# Signal.net
KiCad netlist of a schematic drawn in Altium Designer
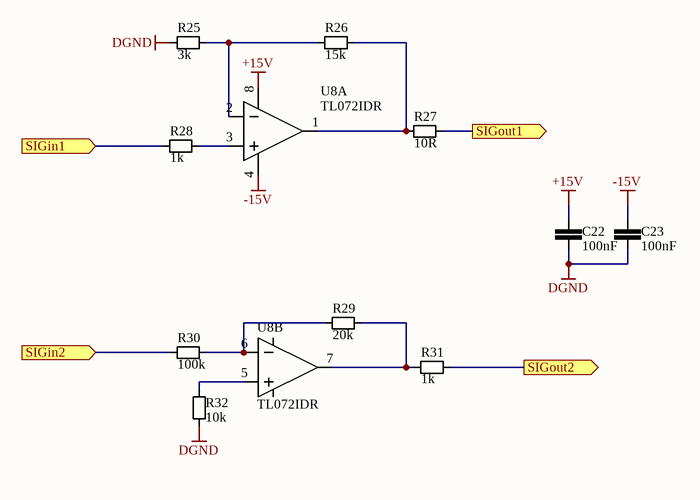
[diagram p0: Signal.SchDoc]

(export (version "E")
  (design (tool "Eeschema 10.0.6"))
  (components
    (comp (ref "C22")
      (value "100nF")
      (footprint "GreenBox:0603-C")
      (description "MLCC 100nF 10% 50V X7R 0603")
      (fields (field (name "Comment") "Cap") (field (name "PUBLISHER") "GreenBox"))
      (libsource (lib "Capacitor") (part "C21C100NK1H0"))
    )
    (comp (ref "C23")
      (value "100nF")
      (footprint "GreenBox:0603-C")
      (description "MLCC 100nF 10% 50V X7R 0603")
      (fields (field (name "Comment") "Cap") (field (name "PUBLISHER") "GreenBox"))
      (libsource (lib "Capacitor") (part "C21C100NK1H0"))
    )
    (comp (ref "R25")
      (value "3k")
      (footprint "GreenBox:0603-R")
      (description "SMD Resistor 3k 1% 1/10W 0603 100PPM")
      (fields (field (name "Comment") "Res") (field (name "PUBLISHER") "GreenBox"))
      (libsource (lib "Resistor") (part "R11C003KFBF0"))
    )
    (comp (ref "R26")
      (value "15k")
      (footprint "GreenBox:0603-R")
      (description "SMD Resistor 15k 1% 1/10W 0603 100PPM")
      (fields (field (name "Comment") "Res") (field (name "PUBLISHER") "GreenBox"))
      (libsource (lib "Resistor") (part "R11C015KFBF0"))
    )
    (comp (ref "R27")
      (value "10R")
      (footprint "GreenBox:0603-R")
      (description "SMD Resistor 10R 1% 1/10W 0603 100PPM")
      (fields (field (name "Comment") "Res") (field (name "PUBLISHER") "GreenBox"))
      (libsource (lib "Resistor") (part "R11C010RFBF0"))
    )
    (comp (ref "R28")
      (value "1k")
      (footprint "GreenBox:0603-R")
      (description "SMD Resistor 1k 1% 1/10W 0603 100PPM")
      (fields (field (name "Comment") "Res") (field (name "PUBLISHER") "GreenBox"))
      (libsource (lib "Resistor") (part "R11C001KFBF0"))
    )
    (comp (ref "R29")
      (value "20k")
      (footprint "GreenBox:0603-R")
      (description "SMD Resistor 20k 1% 1/10W 0603 100PPM")
      (fields (field (name "Comment") "Res") (field (name "PUBLISHER") "GreenBox"))
      (libsource (lib "Resistor") (part "R11C020KFBF0"))
    )
    (comp (ref "R30")
      (value "100k")
      (footprint "GreenBox:0603-R")
      (description "SMD Resistor 100k 1% 1/10W 0603 100PPM")
      (fields (field (name "Comment") "Res") (field (name "PUBLISHER") "GreenBox"))
      (libsource (lib "Resistor") (part "R11C100KFBF0"))
    )
    (comp (ref "R31")
      (value "1k")
      (footprint "GreenBox:0603-R")
      (description "SMD Resistor 1k 1% 1/10W 0603 100PPM")
      (fields (field (name "Comment") "Res") (field (name "PUBLISHER") "GreenBox"))
      (libsource (lib "Resistor") (part "R11C001KFBF0"))
    )
    (comp (ref "R32")
      (value "10k")
      (footprint "GreenBox:0603-R")
      (description "SMD Resistor 10k 1% 1/10W 0603 100PPM")
      (fields (field (name "Comment") "Res") (field (name "PUBLISHER") "GreenBox"))
      (libsource (lib "Resistor") (part "R11C010KFBF0"))
    )
    (comp (ref "U8")
      (value "TL072IDR")
      (footprint "GreenBox:SO-8_N")
      (description "Dual Operational Amplifier TL072IDR Vcc ±18V Vio 3mV")
      (fields (field (name "MANUFACTURER") "TEXAS INSTRUMENTS") (field (name "PUBLISHER") "GreenBox"))
      (libsource (lib "OPAMP") (part "UOS1TLC072IT"))
    )
  )
  (nets
    (net (code "1") (name "+15V") (class "Default")
      (node (ref "C22") (pin "1") (pinfunction "1_1") (pintype "passive"))
      (node (ref "U8") (pin "8") (pintype "passive"))
    )
    (net (code "2") (name "-15V") (class "Default")
      (node (ref "C23") (pin "1") (pinfunction "1_1") (pintype "passive"))
      (node (ref "U8") (pin "4") (pintype "passive"))
    )
    (net (code "3") (name "/SIGin1") (class "Default")
      (node (ref "R28") (pin "1") (pinfunction "1_1") (pintype "passive"))
    )
    (net (code "4") (name "/SIGin2") (class "Default")
      (node (ref "R30") (pin "2") (pinfunction "2_2") (pintype "passive"))
    )
    (net (code "5") (name "/SIGout1") (class "Default")
      (node (ref "R27") (pin "2") (pinfunction "2_2") (pintype "passive"))
    )
    (net (code "6") (name "/SIGout2") (class "Default")
      (node (ref "R31") (pin "2") (pinfunction "2_2") (pintype "passive"))
    )
    (net (code "7") (name "DGND") (class "Default")
      (node (ref "C22") (pin "2") (pinfunction "2_2") (pintype "passive"))
      (node (ref "C23") (pin "2") (pinfunction "2_2") (pintype "passive"))
      (node (ref "R25") (pin "2") (pinfunction "2_2") (pintype "passive"))
      (node (ref "R32") (pin "1") (pinfunction "1_1") (pintype "passive"))
    )
    (net (code "8") (name "Net-(R25-Pad1)") (class "Default")
      (node (ref "R25") (pin "1") (pinfunction "1_1") (pintype "passive"))
      (node (ref "R26") (pin "1") (pinfunction "1_1") (pintype "passive"))
      (node (ref "U8") (pin "2") (pintype "passive"))
    )
    (net (code "9") (name "Net-(R26-Pad2)") (class "Default")
      (node (ref "R26") (pin "2") (pinfunction "2_2") (pintype "passive"))
      (node (ref "R27") (pin "1") (pinfunction "1_1") (pintype "passive"))
      (node (ref "U8") (pin "1") (pintype "passive"))
    )
    (net (code "10") (name "Net-(R28-Pad2)") (class "Default")
      (node (ref "R28") (pin "2") (pinfunction "2_2") (pintype "passive"))
      (node (ref "U8") (pin "3") (pintype "passive"))
    )
    (net (code "11") (name "Net-(R29-Pad1)") (class "Default")
      (node (ref "R29") (pin "1") (pinfunction "1_1") (pintype "passive"))
      (node (ref "R31") (pin "1") (pinfunction "1_1") (pintype "passive"))
      (node (ref "U8") (pin "7") (pintype "passive"))
    )
    (net (code "12") (name "Net-(R29-Pad2)") (class "Default")
      (node (ref "R29") (pin "2") (pinfunction "2_2") (pintype "passive"))
      (node (ref "R30") (pin "1") (pinfunction "1_1") (pintype "passive"))
      (node (ref "U8") (pin "6") (pintype "passive"))
    )
    (net (code "13") (name "Net-(R32-Pad2)") (class "Default")
      (node (ref "R32") (pin "2") (pinfunction "2_2") (pintype "passive"))
      (node (ref "U8") (pin "5") (pintype "passive"))
    )
  )
)
